# BoostConverter.net
KiCad netlist of a schematic drawn in Altium Designer
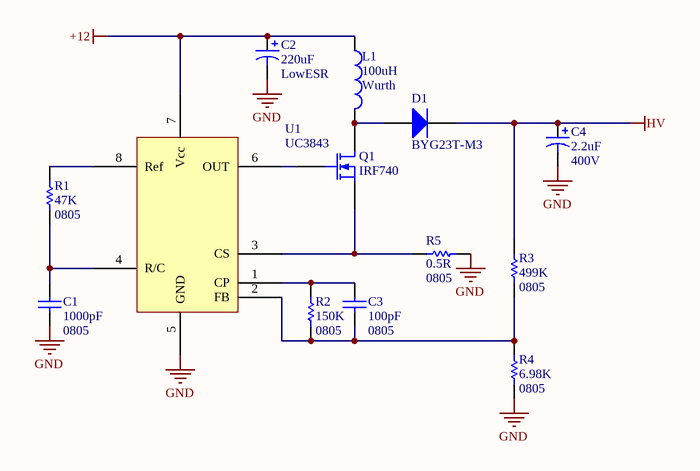
[diagram p0: BoostConverter.SchDoc]

(export (version "E")
  (design (tool "Eeschema 10.0.6"))
  (components
    (comp (ref "C1")
      (value "1000pF")
      (footprint "6-0805_N")
      (description "Capacitor")
      (fields (field (name "ALTIUM_VALUE") "0805") (field (name "PUBLISHER") "Altium Limited"))
      (libsource (lib "Miscellaneous Devices") (part "Cap"))
    )
    (comp (ref "C2")
      (value "220uF")
      (footprint "CapacitorxNichicon")
      (description "Polarized Capacitor (Radial)")
      (fields (field (name "ALTIUM_VALUE") "LowESR") (field (name "PUBLISHER") "Altium Limited"))
      (libsource (lib "Miscellaneous Devices") (part "Cap Pol1"))
    )
    (comp (ref "C3")
      (value "100pF")
      (footprint "6-0805_N")
      (description "Capacitor")
      (fields (field (name "ALTIUM_VALUE") "0805") (field (name "PUBLISHER") "Altium Limited"))
      (libsource (lib "Miscellaneous Devices") (part "Cap"))
    )
    (comp (ref "C4")
      (value "2.2uF")
      (footprint "CAP_UCD_10X10_NCH")
      (description "Polarized Capacitor (Radial)")
      (fields (field (name "ALTIUM_VALUE") "400V") (field (name "PUBLISHER") "Altium Limited"))
      (libsource (lib "Miscellaneous Devices") (part "Cap Pol1"))
    )
    (comp (ref "D1")
      (value "BYG23T-M3")
      (footprint "DIODE_SMA_DO-214AC_VIS")
      (description "Default Diode")
      (fields (field (name "PUBLISHER") "Altium Limited"))
      (libsource (lib "Miscellaneous Devices") (part "Diode"))
    )
    (comp (ref "L1")
      (value "100uH")
      (footprint "inductor12mm")
      (description "Inductor")
      (fields (field (name "ALTIUM_VALUE") "Wurth") (field (name "PUBLISHER") "Altium Limited"))
      (libsource (lib "Miscellaneous Devices") (part "Inductor"))
    )
    (comp (ref "Q1")
      (value "IRF740")
      (footprint "D2PAK_L")
      (description "N-Channel MOSFET")
      (fields (field (name "PUBLISHER") "Altium Limited"))
      (libsource (lib "Miscellaneous Devices") (part "MOSFET-N"))
    )
    (comp (ref "R1")
      (value "47K")
      (footprint "6-0805_N")
      (description "Resistor")
      (fields (field (name "ALTIUM_VALUE") "0805") (field (name "PUBLISHER") "Altium Limited"))
      (libsource (lib "Miscellaneous Devices") (part "Res1"))
    )
    (comp (ref "R2")
      (value "150K")
      (footprint "6-0805_N")
      (description "Resistor")
      (fields (field (name "ALTIUM_VALUE") "0805") (field (name "PUBLISHER") "Altium Limited"))
      (libsource (lib "Miscellaneous Devices") (part "Res1"))
    )
    (comp (ref "R3")
      (value "499K")
      (footprint "6-0805_N")
      (description "Resistor")
      (fields (field (name "ALTIUM_VALUE") "0805") (field (name "PUBLISHER") "Altium Limited"))
      (libsource (lib "Miscellaneous Devices") (part "Res1"))
    )
    (comp (ref "R4")
      (value "6.98K")
      (footprint "6-0805_N")
      (description "Resistor")
      (fields (field (name "ALTIUM_VALUE") "0805") (field (name "PUBLISHER") "Altium Limited"))
      (libsource (lib "Miscellaneous Devices") (part "Res1"))
    )
    (comp (ref "R5")
      (value "0.5R")
      (footprint "6-0805_N")
      (description "Resistor")
      (fields (field (name "ALTIUM_VALUE") "0805") (field (name "PUBLISHER") "Altium Limited"))
      (libsource (lib "Miscellaneous Devices") (part "Res1"))
    )
    (comp (ref "U1")
      (value "UC3843")
      (footprint "UC3843BD1")
      (libsource (lib "CustomComponents") (part "UC3843"))
    )
  )
  (nets
    (net (code "1") (name "+12") (class "Default")
      (node (ref "C2") (pin "1") (pinfunction "1_1") (pintype "passive"))
      (node (ref "L1") (pin "1") (pinfunction "1_1") (pintype "passive"))
      (node (ref "U1") (pin "7") (pinfunction "Vcc_7") (pintype "passive"))
    )
    (net (code "2") (name "GND") (class "Default")
      (node (ref "C1") (pin "1") (pinfunction "1_1") (pintype "passive"))
      (node (ref "C2") (pin "2") (pinfunction "2_2") (pintype "passive"))
      (node (ref "C4") (pin "2") (pinfunction "2_2") (pintype "passive"))
      (node (ref "R4") (pin "1") (pinfunction "1_1") (pintype "passive"))
      (node (ref "R5") (pin "1") (pinfunction "1_1") (pintype "passive"))
      (node (ref "U1") (pin "5") (pinfunction "GND_5") (pintype "passive"))
    )
    (net (code "3") (name "HV") (class "Default")
      (node (ref "C4") (pin "1") (pinfunction "1_1") (pintype "passive"))
      (node (ref "D1") (pin "2") (pinfunction "K_2") (pintype "passive"))
      (node (ref "R3") (pin "2") (pinfunction "2_2") (pintype "passive"))
    )
    (net (code "4") (name "Net-(D1-A)") (class "Default")
      (node (ref "D1") (pin "1") (pinfunction "A_1") (pintype "passive"))
      (node (ref "L1") (pin "2") (pinfunction "2_2") (pintype "passive"))
      (node (ref "Q1") (pin "1") (pinfunction "D_1") (pintype "passive"))
    )
    (net (code "5") (name "Net-(Q1-G)") (class "Default")
      (node (ref "Q1") (pin "2") (pinfunction "G_2") (pintype "passive"))
      (node (ref "U1") (pin "6") (pinfunction "OUT_6") (pintype "passive"))
    )
    (net (code "6") (name "Net-(Q1-S)") (class "Default")
      (node (ref "Q1") (pin "3") (pinfunction "S_3") (pintype "passive"))
      (node (ref "R5") (pin "2") (pinfunction "2_2") (pintype "passive"))
      (node (ref "U1") (pin "3") (pinfunction "CS_3") (pintype "passive"))
    )
    (net (code "7") (name "Net-(U1-CP)") (class "Default")
      (node (ref "C3") (pin "2") (pinfunction "2_2") (pintype "passive"))
      (node (ref "R2") (pin "2") (pinfunction "2_2") (pintype "passive"))
      (node (ref "U1") (pin "1") (pinfunction "CP_1") (pintype "passive"))
    )
    (net (code "8") (name "Net-(U1-FB)") (class "Default")
      (node (ref "C3") (pin "1") (pinfunction "1_1") (pintype "passive"))
      (node (ref "R2") (pin "1") (pinfunction "1_1") (pintype "passive"))
      (node (ref "R3") (pin "1") (pinfunction "1_1") (pintype "passive"))
      (node (ref "R4") (pin "2") (pinfunction "2_2") (pintype "passive"))
      (node (ref "U1") (pin "2") (pinfunction "FB_2") (pintype "passive"))
    )
    (net (code "9") (name "Net-(U1-Ref)") (class "Default")
      (node (ref "R1") (pin "2") (pinfunction "2_2") (pintype "passive"))
      (node (ref "U1") (pin "8") (pinfunction "Ref_8") (pintype "passive"))
    )
    (net (code "10") (name "Net-(U1-R{slash}C)") (class "Default")
      (node (ref "C1") (pin "2") (pinfunction "2_2") (pintype "passive"))
      (node (ref "R1") (pin "1") (pinfunction "1_1") (pintype "passive"))
      (node (ref "U1") (pin "4") (pinfunction "R/C_4") (pintype "passive"))
    )
  )
)
